# BLE-Shield-3_0_0_C1.net
KiCad netlist of a schematic drawn in EAGLE
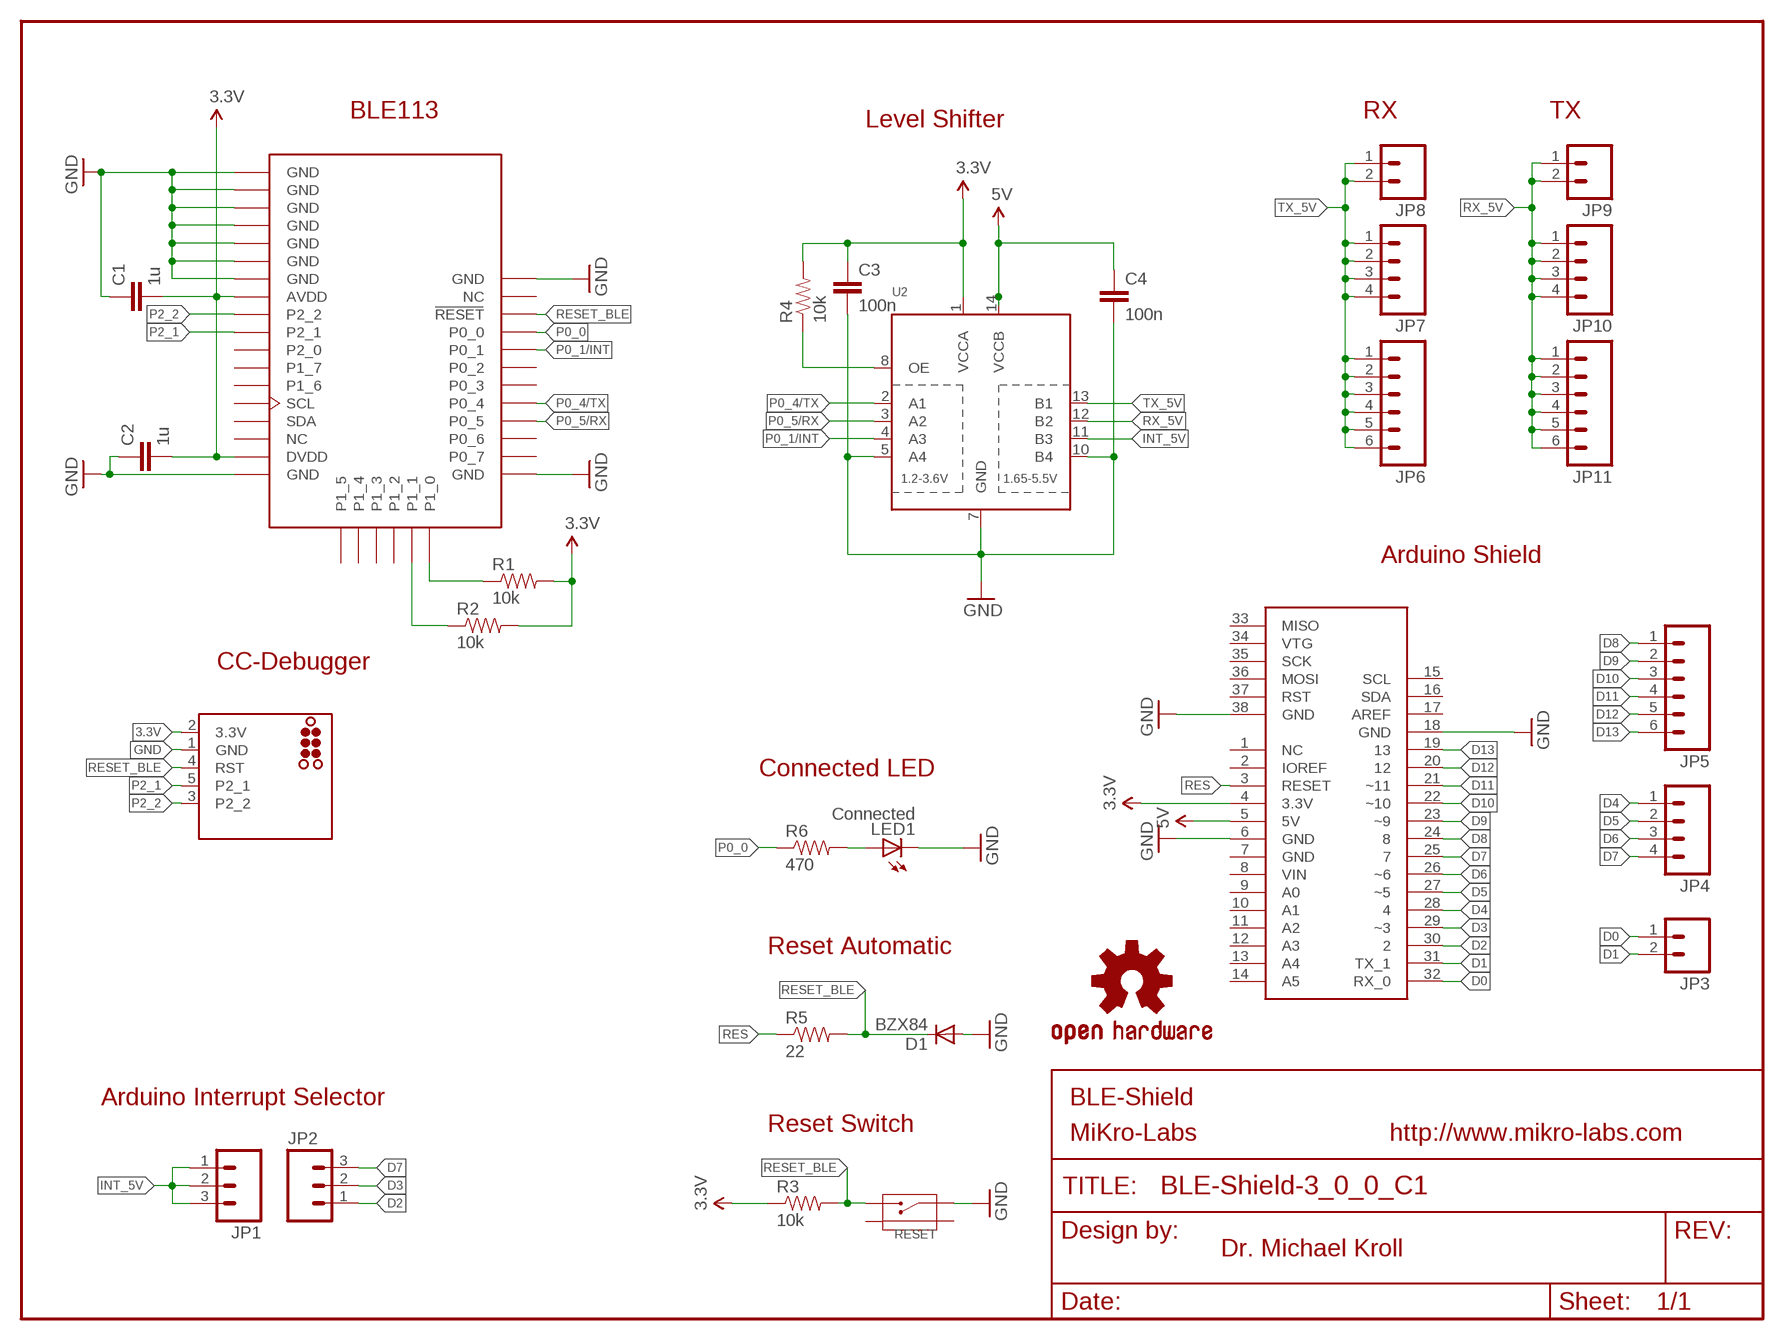
[diagram p0: schematic, sheet 1]

(export (version "E")
  (design (tool "Eeschema 10.0.6"))
  (components
    (comp (ref "C1")
      (value "1u")
      (footprint "eagle-import:0603-CAP")
      (libsource (lib "eagle-import") (part "CAP0603-CAP"))
    )
    (comp (ref "C2")
      (value "1u")
      (footprint "eagle-import:0603-CAP")
      (libsource (lib "eagle-import") (part "CAP0603-CAP"))
    )
    (comp (ref "C3")
      (value "100n")
      (footprint "eagle-import:0603-CAP")
      (libsource (lib "eagle-import") (part "CAP0603-CAP"))
    )
    (comp (ref "C4")
      (value "100n")
      (footprint "eagle-import:0603-CAP")
      (libsource (lib "eagle-import") (part "CAP0603-CAP"))
    )
    (comp (ref "CC-DEBUGGER")
      (value "TC2030-CC-DEBUGGER")
      (footprint "eagle-import:TC2030-MCP-NL")
      (libsource (lib "eagle-import") (part "TC2030-CC-DEBUGGER"))
    )
    (comp (ref "D1")
      (value "BZX84")
      (footprint "eagle-import:SOT23-3")
      (libsource (lib "eagle-import") (part "DIODESOT23"))
    )
    (comp (ref "FRAME1")
      (value "FRAME-LETTER")
      (footprint "eagle-import:CREATIVE_COMMONS")
      (libsource (lib "eagle-import") (part "FRAME-LETTER"))
    )
    (comp (ref "JP1")
      (value "M03PTH")
      (footprint "eagle-import:1X03")
      (libsource (lib "eagle-import") (part "M03PTH"))
    )
    (comp (ref "JP2")
      (value "M03PTH")
      (footprint "eagle-import:1X03")
      (libsource (lib "eagle-import") (part "M03PTH"))
    )
    (comp (ref "JP3")
      (value "M02PTH")
      (footprint "eagle-import:1X02")
      (libsource (lib "eagle-import") (part "M02PTH"))
    )
    (comp (ref "JP4")
      (value "M04PTH")
      (footprint "eagle-import:1X04")
      (libsource (lib "eagle-import") (part "M04PTH"))
    )
    (comp (ref "JP5")
      (value "M06SIP")
      (footprint "eagle-import:1X06")
      (libsource (lib "eagle-import") (part "M06SIP"))
    )
    (comp (ref "JP6")
      (value "M06SIP")
      (footprint "eagle-import:1X06")
      (libsource (lib "eagle-import") (part "M06SIP"))
    )
    (comp (ref "JP7")
      (value "M04PTH")
      (footprint "eagle-import:1X04")
      (libsource (lib "eagle-import") (part "M04PTH"))
    )
    (comp (ref "JP8")
      (value "M02PTH")
      (footprint "eagle-import:1X02")
      (libsource (lib "eagle-import") (part "M02PTH"))
    )
    (comp (ref "JP9")
      (value "M02PTH")
      (footprint "eagle-import:1X02")
      (libsource (lib "eagle-import") (part "M02PTH"))
    )
    (comp (ref "JP10")
      (value "M04PTH")
      (footprint "eagle-import:1X04")
      (libsource (lib "eagle-import") (part "M04PTH"))
    )
    (comp (ref "JP11")
      (value "M06SIP")
      (footprint "eagle-import:1X06")
      (libsource (lib "eagle-import") (part "M06SIP"))
    )
    (comp (ref "LED1")
      (value "Connected")
      (footprint "eagle-import:LED-0603")
      (libsource (lib "eagle-import") (part "LED0603"))
    )
    (comp (ref "LOGO1")
      (value "OSHW-LOGOS")
      (footprint "eagle-import:OSHW-LOGO-S")
      (libsource (lib "eagle-import") (part "OSHW-LOGOS"))
    )
    (comp (ref "R1")
      (value "10k")
      (footprint "eagle-import:0603-RES")
      (libsource (lib "eagle-import") (part "RESISTOR0603-RES"))
    )
    (comp (ref "R2")
      (value "10k")
      (footprint "eagle-import:0603-RES")
      (libsource (lib "eagle-import") (part "RESISTOR0603-RES"))
    )
    (comp (ref "R3")
      (value "10k")
      (footprint "eagle-import:0603-RES")
      (libsource (lib "eagle-import") (part "RESISTOR0603-RES"))
    )
    (comp (ref "R4")
      (value "10k")
      (footprint "eagle-import:0603-RES")
      (libsource (lib "eagle-import") (part "RESISTOR0603-RES"))
    )
    (comp (ref "R5")
      (value "22")
      (footprint "eagle-import:0603-RES")
      (libsource (lib "eagle-import") (part "RESISTOR0603-RES"))
    )
    (comp (ref "R6")
      (value "470")
      (footprint "eagle-import:0603-RES")
      (libsource (lib "eagle-import") (part "RESISTOR0603-RES"))
    )
    (comp (ref "RESET")
      (value "BUTTON-2P-REINFORCE-3100060P1")
      (footprint "eagle-import:4P-SMD-7.0X3.5X3.5H-90D")
      (libsource (lib "eagle-import") (part "BUTTON-2P-REINFORCE-3100060P1"))
    )
    (comp (ref "U$1")
      (value "ARDUINO_UNO_SHIELD_ICSP_PADS_ONLY")
      (footprint "eagle-import:ICSP_PADS_ONLY")
      (libsource (lib "eagle-import") (part "ARDUINO_UNO_SHIELD_ICSP_PADS_ONLY"))
    )
    (comp (ref "U1")
      (value "BLE113-A-VISUAL")
      (footprint "eagle-import:BLE113-A")
      (libsource (lib "eagle-import") (part "BLE113-A-VISUAL"))
    )
    (comp (ref "U2")
      (value "TXB0104PWR")
      (footprint "eagle-import:TSSOP14")
      (libsource (lib "eagle-import") (part "TXB0104PWR"))
    )
  )
  (nets
    (net (code "1") (name "3.3V") (class "Default")
      (node (ref "C1") (pin "2") (pinfunction "2_2") (pintype "passive"))
      (node (ref "C2") (pin "2") (pinfunction "2_2") (pintype "passive"))
      (node (ref "C3") (pin "1") (pinfunction "1_1") (pintype "passive"))
      (node (ref "CC-DEBUGGER") (pin "2") (pinfunction "3.3V_2") (pintype "power_in"))
      (node (ref "R1") (pin "2") (pinfunction "2_2") (pintype "passive"))
      (node (ref "R2") (pin "2") (pinfunction "2_2") (pintype "passive"))
      (node (ref "R3") (pin "1") (pinfunction "1_1") (pintype "passive"))
      (node (ref "R4") (pin "2") (pinfunction "2_2") (pintype "passive"))
      (node (ref "U$1") (pin "4") (pinfunction "3.3V_4") (pintype "bidirectional"))
      (node (ref "U1") (pin "AVDD") (pinfunction "AVDD_AVDD") (pintype "power_in"))
      (node (ref "U1") (pin "DVDD") (pinfunction "DVDD_DVDD") (pintype "power_in"))
      (node (ref "U2") (pin "1") (pinfunction "VCCA_1") (pintype "bidirectional"))
    )
    (net (code "2") (name "5V") (class "Default")
      (node (ref "C4") (pin "1") (pinfunction "1_1") (pintype "passive"))
      (node (ref "U$1") (pin "5") (pinfunction "5V_5") (pintype "bidirectional"))
      (node (ref "U2") (pin "14") (pinfunction "VCCB_14") (pintype "bidirectional"))
    )
    (net (code "3") (name "D0") (class "Default")
      (node (ref "JP3") (pin "1") (pinfunction "1_1") (pintype "passive"))
      (node (ref "U$1") (pin "32") (pinfunction "RX_0_32") (pintype "bidirectional"))
    )
    (net (code "4") (name "D1") (class "Default")
      (node (ref "JP3") (pin "2") (pinfunction "2_2") (pintype "passive"))
      (node (ref "U$1") (pin "31") (pinfunction "TX_1_31") (pintype "bidirectional"))
    )
    (net (code "5") (name "D2") (class "Default")
      (node (ref "JP2") (pin "1") (pinfunction "1_1") (pintype "passive"))
      (node (ref "U$1") (pin "30") (pinfunction "2_30") (pintype "bidirectional"))
    )
    (net (code "6") (name "D3") (class "Default")
      (node (ref "JP2") (pin "2") (pinfunction "2_2") (pintype "passive"))
      (node (ref "U$1") (pin "29") (pinfunction "~{3}_29") (pintype "bidirectional"))
    )
    (net (code "7") (name "D4") (class "Default")
      (node (ref "JP4") (pin "1") (pinfunction "1_1") (pintype "passive"))
      (node (ref "U$1") (pin "28") (pinfunction "4_28") (pintype "bidirectional"))
    )
    (net (code "8") (name "D5") (class "Default")
      (node (ref "JP4") (pin "2") (pinfunction "2_2") (pintype "passive"))
      (node (ref "U$1") (pin "27") (pinfunction "~{5}_27") (pintype "bidirectional"))
    )
    (net (code "9") (name "D6") (class "Default")
      (node (ref "JP4") (pin "3") (pinfunction "3_3") (pintype "passive"))
      (node (ref "U$1") (pin "26") (pinfunction "~{6}_26") (pintype "bidirectional"))
    )
    (net (code "10") (name "D7") (class "Default")
      (node (ref "JP2") (pin "3") (pinfunction "3_3") (pintype "passive"))
      (node (ref "JP4") (pin "4") (pinfunction "4_4") (pintype "passive"))
      (node (ref "U$1") (pin "25") (pinfunction "7_25") (pintype "bidirectional"))
    )
    (net (code "11") (name "D8") (class "Default")
      (node (ref "JP5") (pin "1") (pinfunction "1_1") (pintype "passive"))
      (node (ref "U$1") (pin "24") (pinfunction "8_24") (pintype "bidirectional"))
    )
    (net (code "12") (name "D9") (class "Default")
      (node (ref "JP5") (pin "2") (pinfunction "2_2") (pintype "passive"))
      (node (ref "U$1") (pin "23") (pinfunction "~{9}_23") (pintype "bidirectional"))
    )
    (net (code "13") (name "D10") (class "Default")
      (node (ref "JP5") (pin "3") (pinfunction "3_3") (pintype "passive"))
      (node (ref "U$1") (pin "22") (pinfunction "~{10}_22") (pintype "bidirectional"))
    )
    (net (code "14") (name "D11") (class "Default")
      (node (ref "JP5") (pin "4") (pinfunction "4_4") (pintype "passive"))
      (node (ref "U$1") (pin "21") (pinfunction "~{11}_21") (pintype "bidirectional"))
    )
    (net (code "15") (name "D12") (class "Default")
      (node (ref "JP5") (pin "5") (pinfunction "5_5") (pintype "passive"))
      (node (ref "U$1") (pin "20") (pinfunction "12_20") (pintype "bidirectional"))
    )
    (net (code "16") (name "D13") (class "Default")
      (node (ref "JP5") (pin "6") (pinfunction "6_6") (pintype "passive"))
      (node (ref "U$1") (pin "19") (pinfunction "13_19") (pintype "bidirectional"))
    )
    (net (code "17") (name "GND") (class "Default")
      (node (ref "C1") (pin "1") (pinfunction "1_1") (pintype "passive"))
      (node (ref "C2") (pin "1") (pinfunction "1_1") (pintype "passive"))
      (node (ref "C3") (pin "2") (pinfunction "2_2") (pintype "passive"))
      (node (ref "C4") (pin "2") (pinfunction "2_2") (pintype "passive"))
      (node (ref "CC-DEBUGGER") (pin "1") (pinfunction "GND_1") (pintype "power_in"))
      (node (ref "D1") (pin "1") (pinfunction "A_1") (pintype "passive"))
      (node (ref "LED1") (pin "C") (pinfunction "C_C") (pintype "passive"))
      (node (ref "RESET") (pin "1") (pinfunction "1_1") (pintype "bidirectional"))
      (node (ref "U$1") (pin "18") (pinfunction "GND_18") (pintype "bidirectional"))
      (node (ref "U$1") (pin "38") (pinfunction "GND_38") (pintype "bidirectional"))
      (node (ref "U$1") (pin "6") (pinfunction "GND_6") (pintype "bidirectional"))
      (node (ref "U1") (pin "GND") (pinfunction "GND_GND") (pintype "power_in"))
      (node (ref "U1") (pin "GND@10") (pinfunction "GND_GND@10") (pintype "power_in"))
      (node (ref "U1") (pin "GND@2") (pinfunction "GND_GND@2") (pintype "power_in"))
      (node (ref "U1") (pin "GND@3") (pinfunction "GND_GND@3") (pintype "power_in"))
      (node (ref "U1") (pin "GND@4") (pinfunction "GND_GND@4") (pintype "power_in"))
      (node (ref "U1") (pin "GND@5") (pinfunction "GND_GND@5") (pintype "power_in"))
      (node (ref "U1") (pin "GND@6") (pinfunction "GND_GND@6") (pintype "power_in"))
      (node (ref "U1") (pin "GND@7") (pinfunction "GND_GND@7") (pintype "power_in"))
      (node (ref "U1") (pin "GND@8") (pinfunction "GND_GND@8") (pintype "power_in"))
      (node (ref "U1") (pin "GND@9") (pinfunction "GND_GND@9") (pintype "power_in"))
      (node (ref "U2") (pin "10") (pinfunction "B4_10") (pintype "bidirectional"))
      (node (ref "U2") (pin "5") (pinfunction "A4_5") (pintype "bidirectional"))
      (node (ref "U2") (pin "7") (pinfunction "GND_7") (pintype "bidirectional"))
    )
    (net (code "18") (name "INT_5V") (class "Default")
      (node (ref "JP1") (pin "1") (pinfunction "1_1") (pintype "passive"))
      (node (ref "JP1") (pin "2") (pinfunction "2_2") (pintype "passive"))
      (node (ref "JP1") (pin "3") (pinfunction "3_3") (pintype "passive"))
      (node (ref "U2") (pin "11") (pinfunction "B3_11") (pintype "bidirectional"))
    )
    (net (code "19") (name "Net-(LED1-PadA)") (class "Default")
      (node (ref "LED1") (pin "A") (pinfunction "A_A") (pintype "passive"))
      (node (ref "R6") (pin "2") (pinfunction "2_2") (pintype "passive"))
    )
    (net (code "20") (name "Net-(R1-Pad1)") (class "Default")
      (node (ref "R1") (pin "1") (pinfunction "1_1") (pintype "passive"))
      (node (ref "U1") (pin "P1_0") (pinfunction "P1_0_P1_0") (pintype "bidirectional"))
    )
    (net (code "21") (name "Net-(R2-Pad1)") (class "Default")
      (node (ref "R2") (pin "1") (pinfunction "1_1") (pintype "passive"))
      (node (ref "U1") (pin "P1_1") (pinfunction "P1_1_P1_1") (pintype "bidirectional"))
    )
    (net (code "22") (name "Net-(U2-OE)") (class "Default")
      (node (ref "R4") (pin "1") (pinfunction "1_1") (pintype "passive"))
      (node (ref "U2") (pin "8") (pinfunction "OE_8") (pintype "bidirectional"))
    )
    (net (code "23") (name "P0_0") (class "Default")
      (node (ref "R6") (pin "1") (pinfunction "1_1") (pintype "passive"))
      (node (ref "U1") (pin "P0_0") (pinfunction "P0_0_P0_0") (pintype "bidirectional"))
    )
    (net (code "24") (name "P0_1{slash}INT") (class "Default")
      (node (ref "U1") (pin "P0_1") (pinfunction "P0_1_P0_1") (pintype "bidirectional"))
      (node (ref "U2") (pin "4") (pinfunction "A3_4") (pintype "bidirectional"))
    )
    (net (code "25") (name "P0_4{slash}TX") (class "Default")
      (node (ref "U1") (pin "P0_4") (pinfunction "P0_4_P0_4") (pintype "bidirectional"))
      (node (ref "U2") (pin "2") (pinfunction "A1_2") (pintype "bidirectional"))
    )
    (net (code "26") (name "P0_5{slash}RX") (class "Default")
      (node (ref "U1") (pin "P0_5") (pinfunction "P0_5_P0_5") (pintype "bidirectional"))
      (node (ref "U2") (pin "3") (pinfunction "A2_3") (pintype "bidirectional"))
    )
    (net (code "27") (name "P2_1") (class "Default")
      (node (ref "CC-DEBUGGER") (pin "5") (pinfunction "P2_1_5") (pintype "bidirectional"))
      (node (ref "U1") (pin "P2_1") (pinfunction "P2_1_P2_1") (pintype "bidirectional"))
    )
    (net (code "28") (name "P2_2") (class "Default")
      (node (ref "CC-DEBUGGER") (pin "3") (pinfunction "P2_2_3") (pintype "bidirectional"))
      (node (ref "U1") (pin "P2_2") (pinfunction "P2_2_P2_2") (pintype "bidirectional"))
    )
    (net (code "29") (name "RES") (class "Default")
      (node (ref "R5") (pin "1") (pinfunction "1_1") (pintype "passive"))
      (node (ref "U$1") (pin "3") (pinfunction "RESET_3") (pintype "bidirectional"))
    )
    (net (code "30") (name "RESET_BLE") (class "Default")
      (node (ref "CC-DEBUGGER") (pin "4") (pinfunction "RST_4") (pintype "bidirectional"))
      (node (ref "D1") (pin "3") (pinfunction "C_3") (pintype "passive"))
      (node (ref "R3") (pin "2") (pinfunction "2_2") (pintype "passive"))
      (node (ref "R5") (pin "2") (pinfunction "2_2") (pintype "passive"))
      (node (ref "RESET") (pin "2") (pinfunction "2_2") (pintype "bidirectional"))
      (node (ref "U1") (pin "RESET") (pinfunction "RESET_RESET") (pintype "input"))
    )
    (net (code "31") (name "RX_5V") (class "Default")
      (node (ref "JP10") (pin "1") (pinfunction "1_1") (pintype "passive"))
      (node (ref "JP10") (pin "2") (pinfunction "2_2") (pintype "passive"))
      (node (ref "JP10") (pin "3") (pinfunction "3_3") (pintype "passive"))
      (node (ref "JP10") (pin "4") (pinfunction "4_4") (pintype "passive"))
      (node (ref "JP11") (pin "1") (pinfunction "1_1") (pintype "passive"))
      (node (ref "JP11") (pin "2") (pinfunction "2_2") (pintype "passive"))
      (node (ref "JP11") (pin "3") (pinfunction "3_3") (pintype "passive"))
      (node (ref "JP11") (pin "4") (pinfunction "4_4") (pintype "passive"))
      (node (ref "JP11") (pin "5") (pinfunction "5_5") (pintype "passive"))
      (node (ref "JP11") (pin "6") (pinfunction "6_6") (pintype "passive"))
      (node (ref "JP9") (pin "1") (pinfunction "1_1") (pintype "passive"))
      (node (ref "JP9") (pin "2") (pinfunction "2_2") (pintype "passive"))
      (node (ref "U2") (pin "12") (pinfunction "B2_12") (pintype "bidirectional"))
    )
    (net (code "32") (name "TX_5V") (class "Default")
      (node (ref "JP6") (pin "1") (pinfunction "1_1") (pintype "passive"))
      (node (ref "JP6") (pin "2") (pinfunction "2_2") (pintype "passive"))
      (node (ref "JP6") (pin "3") (pinfunction "3_3") (pintype "passive"))
      (node (ref "JP6") (pin "4") (pinfunction "4_4") (pintype "passive"))
      (node (ref "JP6") (pin "5") (pinfunction "5_5") (pintype "passive"))
      (node (ref "JP6") (pin "6") (pinfunction "6_6") (pintype "passive"))
      (node (ref "JP7") (pin "1") (pinfunction "1_1") (pintype "passive"))
      (node (ref "JP7") (pin "2") (pinfunction "2_2") (pintype "passive"))
      (node (ref "JP7") (pin "3") (pinfunction "3_3") (pintype "passive"))
      (node (ref "JP7") (pin "4") (pinfunction "4_4") (pintype "passive"))
      (node (ref "JP8") (pin "1") (pinfunction "1_1") (pintype "passive"))
      (node (ref "JP8") (pin "2") (pinfunction "2_2") (pintype "passive"))
      (node (ref "U2") (pin "13") (pinfunction "B1_13") (pintype "bidirectional"))
    )
    (net (code "33") (name "unconnected-(RESET-PadS1)") (class "Default")
      (node (ref "RESET") (pin "S1") (pinfunction "S1_S1") (pintype "bidirectional"))
    )
    (net (code "34") (name "unconnected-(RESET-PadS2)") (class "Default")
      (node (ref "RESET") (pin "S2") (pinfunction "S2_S2") (pintype "bidirectional"))
    )
    (net (code "35") (name "unconnected-(U$1-A0-Pad9)") (class "Default")
      (node (ref "U$1") (pin "9") (pinfunction "A0_9") (pintype "bidirectional"))
    )
    (net (code "36") (name "unconnected-(U$1-A1-Pad10)") (class "Default")
      (node (ref "U$1") (pin "10") (pinfunction "A1_10") (pintype "bidirectional"))
    )
    (net (code "37") (name "unconnected-(U$1-A2-Pad11)") (class "Default")
      (node (ref "U$1") (pin "11") (pinfunction "A2_11") (pintype "bidirectional"))
    )
    (net (code "38") (name "unconnected-(U$1-A3-Pad12)") (class "Default")
      (node (ref "U$1") (pin "12") (pinfunction "A3_12") (pintype "bidirectional"))
    )
    (net (code "39") (name "unconnected-(U$1-A4-Pad13)") (class "Default")
      (node (ref "U$1") (pin "13") (pinfunction "A4_13") (pintype "bidirectional"))
    )
    (net (code "40") (name "unconnected-(U$1-A5-Pad14)") (class "Default")
      (node (ref "U$1") (pin "14") (pinfunction "A5_14") (pintype "bidirectional"))
    )
    (net (code "41") (name "unconnected-(U$1-AREF-Pad17)") (class "Default")
      (node (ref "U$1") (pin "17") (pinfunction "AREF_17") (pintype "bidirectional"))
    )
    (net (code "42") (name "unconnected-(U$1-GND-Pad7)") (class "Default")
      (node (ref "U$1") (pin "7") (pinfunction "GND_7") (pintype "bidirectional"))
    )
    (net (code "43") (name "unconnected-(U$1-IOREF-Pad2)") (class "Default")
      (node (ref "U$1") (pin "2") (pinfunction "IOREF_2") (pintype "bidirectional"))
    )
    (net (code "44") (name "unconnected-(U$1-MISO-Pad33)") (class "Default")
      (node (ref "U$1") (pin "33") (pinfunction "MISO_33") (pintype "bidirectional"))
    )
    (net (code "45") (name "unconnected-(U$1-MOSI-Pad36)") (class "Default")
      (node (ref "U$1") (pin "36") (pinfunction "MOSI_36") (pintype "bidirectional"))
    )
    (net (code "46") (name "unconnected-(U$1-NC-Pad1)") (class "Default")
      (node (ref "U$1") (pin "1") (pinfunction "NC_1") (pintype "no_connect"))
    )
    (net (code "47") (name "unconnected-(U$1-RST-Pad37)") (class "Default")
      (node (ref "U$1") (pin "37") (pinfunction "RST_37") (pintype "bidirectional"))
    )
    (net (code "48") (name "unconnected-(U$1-SCK-Pad35)") (class "Default")
      (node (ref "U$1") (pin "35") (pinfunction "SCK_35") (pintype "bidirectional"))
    )
    (net (code "49") (name "unconnected-(U$1-SCL-Pad15)") (class "Default")
      (node (ref "U$1") (pin "15") (pinfunction "SCL_15") (pintype "bidirectional"))
    )
    (net (code "50") (name "unconnected-(U$1-SDA-Pad16)") (class "Default")
      (node (ref "U$1") (pin "16") (pinfunction "SDA_16") (pintype "bidirectional"))
    )
    (net (code "51") (name "unconnected-(U$1-VIN-Pad8)") (class "Default")
      (node (ref "U$1") (pin "8") (pinfunction "VIN_8") (pintype "bidirectional"))
    )
    (net (code "52") (name "unconnected-(U$1-VTG-Pad34)") (class "Default")
      (node (ref "U$1") (pin "34") (pinfunction "VTG_34") (pintype "bidirectional"))
    )
    (net (code "53") (name "unconnected-(U1-NC-PadNC@2)") (class "Default")
      (node (ref "U1") (pin "NC@2") (pinfunction "NC_NC@2") (pintype "no_connect"))
    )
    (net (code "54") (name "unconnected-(U1-PadNC)") (class "Default")
      (node (ref "U1") (pin "NC") (pinfunction "NC_NC") (pintype "no_connect"))
    )
    (net (code "55") (name "unconnected-(U1-PadP0_2)") (class "Default")
      (node (ref "U1") (pin "P0_2") (pinfunction "P0_2_P0_2") (pintype "bidirectional"))
    )
    (net (code "56") (name "unconnected-(U1-PadP0_3)") (class "Default")
      (node (ref "U1") (pin "P0_3") (pinfunction "P0_3_P0_3") (pintype "bidirectional"))
    )
    (net (code "57") (name "unconnected-(U1-PadP0_6)") (class "Default")
      (node (ref "U1") (pin "P0_6") (pinfunction "P0_6_P0_6") (pintype "bidirectional"))
    )
    (net (code "58") (name "unconnected-(U1-PadP0_7)") (class "Default")
      (node (ref "U1") (pin "P0_7") (pinfunction "P0_7_P0_7") (pintype "bidirectional"))
    )
    (net (code "59") (name "unconnected-(U1-PadP1_2)") (class "Default")
      (node (ref "U1") (pin "P1_2") (pinfunction "P1_2_P1_2") (pintype "bidirectional"))
    )
    (net (code "60") (name "unconnected-(U1-PadP1_3)") (class "Default")
      (node (ref "U1") (pin "P1_3") (pinfunction "P1_3_P1_3") (pintype "bidirectional"))
    )
    (net (code "61") (name "unconnected-(U1-PadP1_4)") (class "Default")
      (node (ref "U1") (pin "P1_4") (pinfunction "P1_4_P1_4") (pintype "bidirectional"))
    )
    (net (code "62") (name "unconnected-(U1-PadP1_5)") (class "Default")
      (node (ref "U1") (pin "P1_5") (pinfunction "P1_5_P1_5") (pintype "bidirectional"))
    )
    (net (code "63") (name "unconnected-(U1-PadP1_6)") (class "Default")
      (node (ref "U1") (pin "P1_6") (pinfunction "P1_6_P1_6") (pintype "bidirectional"))
    )
    (net (code "64") (name "unconnected-(U1-PadP1_7)") (class "Default")
      (node (ref "U1") (pin "P1_7") (pinfunction "P1_7_P1_7") (pintype "bidirectional"))
    )
    (net (code "65") (name "unconnected-(U1-PadP2_0)") (class "Default")
      (node (ref "U1") (pin "P2_0") (pinfunction "P2_0_P2_0") (pintype "bidirectional"))
    )
    (net (code "66") (name "unconnected-(U1-PadSCL)") (class "Default")
      (node (ref "U1") (pin "SCL") (pinfunction "SCL_SCL") (pintype "bidirectional"))
    )
    (net (code "67") (name "unconnected-(U1-PadSDA)") (class "Default")
      (node (ref "U1") (pin "SDA") (pinfunction "SDA_SDA") (pintype "bidirectional"))
    )
  )
)
